# dabpi__v11.net
KiCad netlist of a schematic drawn in EAGLE
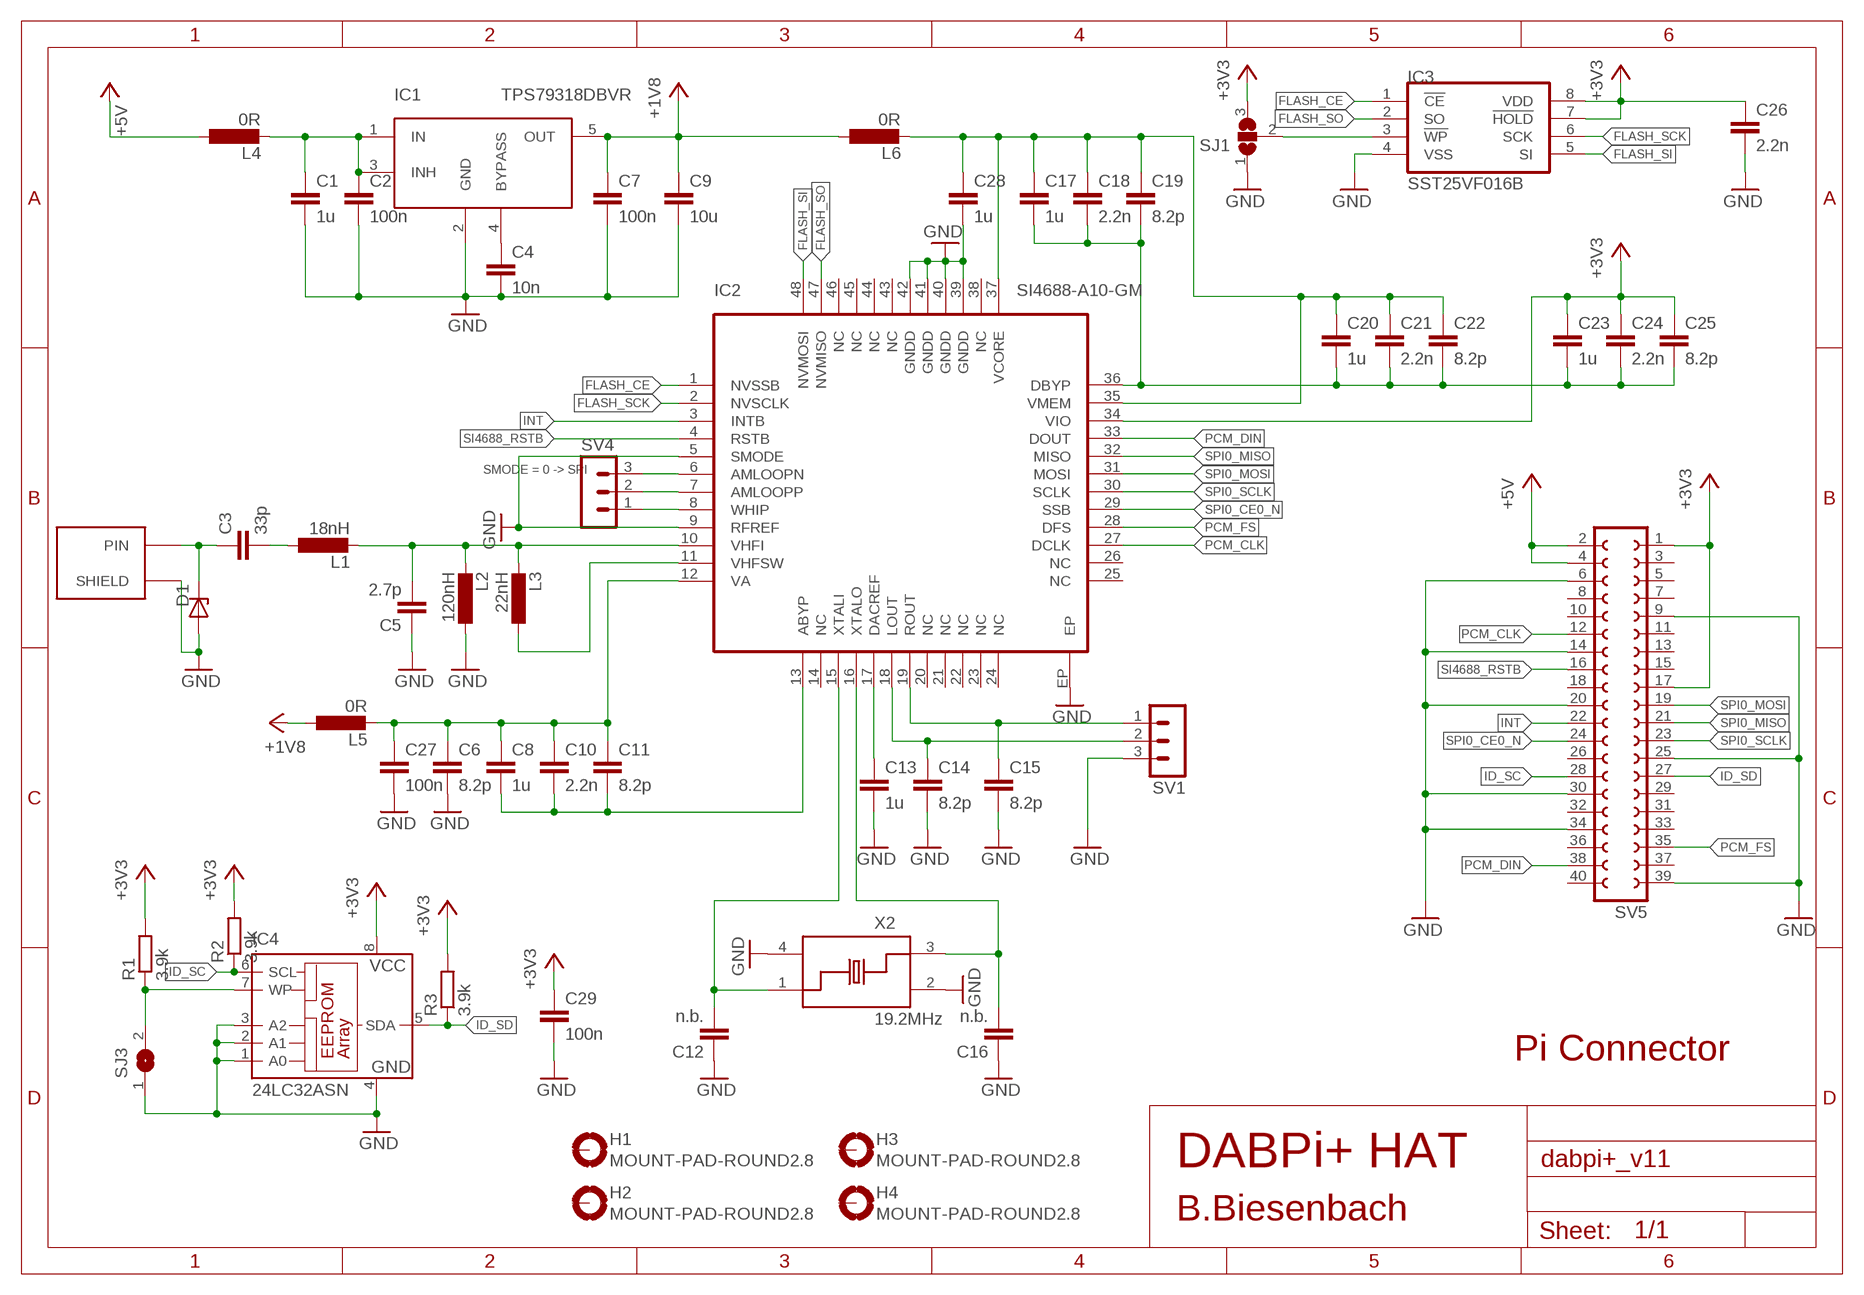
[diagram p0: schematic, sheet 1]

(export (version "E")
  (design (tool "Eeschema 10.0.6"))
  (components
    (comp (ref "C1")
      (value "1u")
      (footprint "eagle-import:SMD0603")
      (libsource (lib "eagle-import") (part "C0603"))
    )
    (comp (ref "C2")
      (value "100n")
      (footprint "eagle-import:SMD0603")
      (libsource (lib "eagle-import") (part "C0603"))
    )
    (comp (ref "C3")
      (value "33p")
      (footprint "eagle-import:SMD0402")
      (libsource (lib "eagle-import") (part "C0402"))
    )
    (comp (ref "C4")
      (value "10n")
      (footprint "eagle-import:SMD0603")
      (libsource (lib "eagle-import") (part "C0603"))
    )
    (comp (ref "C5")
      (value "2.7p")
      (footprint "eagle-import:SMD0402")
      (libsource (lib "eagle-import") (part "C0402"))
    )
    (comp (ref "C6")
      (value "8.2p")
      (footprint "eagle-import:SMD0603")
      (libsource (lib "eagle-import") (part "C0603"))
    )
    (comp (ref "C7")
      (value "100n")
      (footprint "eagle-import:SMD0603")
      (libsource (lib "eagle-import") (part "C0603"))
    )
    (comp (ref "C8")
      (value "1u")
      (footprint "eagle-import:SMD0603")
      (libsource (lib "eagle-import") (part "C0603"))
    )
    (comp (ref "C9")
      (value "10u")
      (footprint "eagle-import:SMD0603")
      (libsource (lib "eagle-import") (part "C0603"))
    )
    (comp (ref "C10")
      (value "2.2n")
      (footprint "eagle-import:SMD0603")
      (libsource (lib "eagle-import") (part "C0603"))
    )
    (comp (ref "C11")
      (value "8.2p")
      (footprint "eagle-import:SMD0603")
      (libsource (lib "eagle-import") (part "C0603"))
    )
    (comp (ref "C12")
      (value "n.b.")
      (footprint "eagle-import:SMD0402")
      (libsource (lib "eagle-import") (part "C0402"))
    )
    (comp (ref "C13")
      (value "1u")
      (footprint "eagle-import:SMD0603")
      (libsource (lib "eagle-import") (part "C0603"))
    )
    (comp (ref "C14")
      (value "8.2p")
      (footprint "eagle-import:SMD0603")
      (libsource (lib "eagle-import") (part "C0603"))
    )
    (comp (ref "C15")
      (value "8.2p")
      (footprint "eagle-import:SMD0603")
      (libsource (lib "eagle-import") (part "C0603"))
    )
    (comp (ref "C16")
      (value "n.b.")
      (footprint "eagle-import:SMD0402")
      (libsource (lib "eagle-import") (part "C0402"))
    )
    (comp (ref "C17")
      (value "1u")
      (footprint "eagle-import:SMD0603")
      (libsource (lib "eagle-import") (part "C0603"))
    )
    (comp (ref "C18")
      (value "2.2n")
      (footprint "eagle-import:SMD0603")
      (libsource (lib "eagle-import") (part "C0603"))
    )
    (comp (ref "C19")
      (value "8.2p")
      (footprint "eagle-import:SMD0603")
      (libsource (lib "eagle-import") (part "C0603"))
    )
    (comp (ref "C20")
      (value "1u")
      (footprint "eagle-import:SMD0603")
      (libsource (lib "eagle-import") (part "C0603"))
    )
    (comp (ref "C21")
      (value "2.2n")
      (footprint "eagle-import:SMD0603")
      (libsource (lib "eagle-import") (part "C0603"))
    )
    (comp (ref "C22")
      (value "8.2p")
      (footprint "eagle-import:SMD0603")
      (libsource (lib "eagle-import") (part "C0603"))
    )
    (comp (ref "C23")
      (value "1u")
      (footprint "eagle-import:SMD0603")
      (libsource (lib "eagle-import") (part "C0603"))
    )
    (comp (ref "C24")
      (value "2.2n")
      (footprint "eagle-import:SMD0603")
      (libsource (lib "eagle-import") (part "C0603"))
    )
    (comp (ref "C25")
      (value "8.2p")
      (footprint "eagle-import:SMD0603")
      (libsource (lib "eagle-import") (part "C0603"))
    )
    (comp (ref "C26")
      (value "2.2n")
      (footprint "eagle-import:SMD0603")
      (libsource (lib "eagle-import") (part "C0603"))
    )
    (comp (ref "C27")
      (value "100n")
      (footprint "eagle-import:SMD0603")
      (libsource (lib "eagle-import") (part "C0603"))
    )
    (comp (ref "C28")
      (value "1u")
      (footprint "eagle-import:SMD0603")
      (libsource (lib "eagle-import") (part "C0603"))
    )
    (comp (ref "C29")
      (value "100n")
      (footprint "eagle-import:SMD0603")
      (libsource (lib "eagle-import") (part "C0603"))
    )
    (comp (ref "D1")
      (value "ESD9L5.0")
      (footprint "eagle-import:SOD923")
      (libsource (lib "eagle-import") (part "ESD9L5.0"))
    )
    (comp (ref "H1")
      (value "MOUNT-PAD-ROUND2.8")
      (footprint "eagle-import:2,8-PAD")
      (libsource (lib "eagle-import") (part "MOUNT-PAD-ROUND2.8"))
    )
    (comp (ref "H2")
      (value "MOUNT-PAD-ROUND2.8")
      (footprint "eagle-import:2,8-PAD")
      (libsource (lib "eagle-import") (part "MOUNT-PAD-ROUND2.8"))
    )
    (comp (ref "H3")
      (value "MOUNT-PAD-ROUND2.8")
      (footprint "eagle-import:2,8-PAD")
      (libsource (lib "eagle-import") (part "MOUNT-PAD-ROUND2.8"))
    )
    (comp (ref "H4")
      (value "MOUNT-PAD-ROUND2.8")
      (footprint "eagle-import:2,8-PAD")
      (libsource (lib "eagle-import") (part "MOUNT-PAD-ROUND2.8"))
    )
    (comp (ref "IC1")
      (value "TPS79318DBVR")
      (footprint "eagle-import:SOT23-5")
      (libsource (lib "eagle-import") (part "TPS79318DBVR"))
    )
    (comp (ref "IC2")
      (value "SI4688-A10-GM")
      (footprint "eagle-import:QFN48")
      (libsource (lib "eagle-import") (part "SI4688-A10-GM"))
    )
    (comp (ref "IC3")
      (value "SST25VF016B")
      (footprint "eagle-import:SO08")
      (libsource (lib "eagle-import") (part "SST25VF016B"))
    )
    (comp (ref "IC4")
      (value "24LC32ASN")
      (footprint "eagle-import:SO-08")
      (fields (field (name "MF") "MICROCHIP") (field (name "MPN") "24LC32A/SN"))
      (libsource (lib "eagle-import") (part "24SNLC32A"))
    )
    (comp (ref "L1")
      (value "18nH")
      (footprint "eagle-import:SMD0402")
      (libsource (lib "eagle-import") (part "L0402"))
    )
    (comp (ref "L2")
      (value "120nH")
      (footprint "eagle-import:SMD0402")
      (libsource (lib "eagle-import") (part "L0402"))
    )
    (comp (ref "L3")
      (value "22nH")
      (footprint "eagle-import:SMD0402")
      (libsource (lib "eagle-import") (part "L0402"))
    )
    (comp (ref "L4")
      (value "0R")
      (footprint "eagle-import:SMD0603")
      (libsource (lib "eagle-import") (part "L0603"))
    )
    (comp (ref "L5")
      (value "0R")
      (footprint "eagle-import:SMD0603")
      (libsource (lib "eagle-import") (part "L0603"))
    )
    (comp (ref "L6")
      (value "0R")
      (footprint "eagle-import:SMD0603")
      (libsource (lib "eagle-import") (part "L0603"))
    )
    (comp (ref "R1")
      (value "3.9k")
      (footprint "eagle-import:SMD0603")
      (libsource (lib "eagle-import") (part "R0603"))
    )
    (comp (ref "R2")
      (value "3.9k")
      (footprint "eagle-import:SMD0603")
      (libsource (lib "eagle-import") (part "R0603"))
    )
    (comp (ref "R3")
      (value "3.9k")
      (footprint "eagle-import:SMD0603")
      (libsource (lib "eagle-import") (part "R0603"))
    )
    (comp (ref "SJ1")
      (value "SJ2W")
      (footprint "eagle-import:SJ_2")
      (libsource (lib "eagle-import") (part "SJ2W"))
    )
    (comp (ref "SJ3") (value "SJ") (footprint "eagle-import:SJ") (libsource (lib "eagle-import") (part "SJ")))
    (comp (ref "SV1")
      (value "MA03-1")
      (footprint "eagle-import:MA03-1")
      (libsource (lib "eagle-import") (part "MA03-1"))
    )
    (comp (ref "SV4")
      (value "MA03-1")
      (footprint "eagle-import:MA03-1")
      (libsource (lib "eagle-import") (part "MA03-1"))
    )
    (comp (ref "SV5")
      (value "FE20-2")
      (footprint "eagle-import:FE20-2")
      (libsource (lib "eagle-import") (part "FE20-2"))
    )
    (comp (ref "X1")
      (value "SMA_LP_1.57MM")
      (footprint "eagle-import:SMA_LP_1.57MM")
      (libsource (lib "eagle-import") (part "SMA_LP_1.57MM"))
    )
    (comp (ref "X2")
      (value "19.2MHz")
      (footprint "eagle-import:XTAL_3.2X2.5")
      (libsource (lib "eagle-import") (part "XTAL_3.2X2.5"))
    )
  )
  (nets
    (net (code "1") (name "+1V8") (class "Default")
      (node (ref "C7") (pin "1") (pinfunction "1_1") (pintype "passive"))
      (node (ref "C9") (pin "1") (pinfunction "1_1") (pintype "passive"))
      (node (ref "IC1") (pin "5") (pinfunction "OUT_5") (pintype "power_in"))
      (node (ref "L5") (pin "1") (pinfunction "1_1") (pintype "passive"))
      (node (ref "L6") (pin "1") (pinfunction "1_1") (pintype "passive"))
    )
    (net (code "2") (name "+3V3") (class "Default")
      (node (ref "C23") (pin "1") (pinfunction "1_1") (pintype "passive"))
      (node (ref "C24") (pin "1") (pinfunction "1_1") (pintype "passive"))
      (node (ref "C25") (pin "1") (pinfunction "1_1") (pintype "passive"))
      (node (ref "C26") (pin "1") (pinfunction "1_1") (pintype "passive"))
      (node (ref "C29") (pin "1") (pinfunction "1_1") (pintype "passive"))
      (node (ref "IC2") (pin "34") (pinfunction "VIO_34") (pintype "power_in"))
      (node (ref "IC3") (pin "7") (pinfunction "~{HOLD}_7") (pintype "input"))
      (node (ref "IC3") (pin "8") (pinfunction "VDD_8") (pintype "power_in"))
      (node (ref "IC4") (pin "8") (pinfunction "VCC_8") (pintype "power_in"))
      (node (ref "R1") (pin "2") (pinfunction "2_2") (pintype "passive"))
      (node (ref "R2") (pin "2") (pinfunction "2_2") (pintype "passive"))
      (node (ref "R3") (pin "2") (pinfunction "2_2") (pintype "passive"))
      (node (ref "SJ1") (pin "3") (pinfunction "3_3") (pintype "passive"))
      (node (ref "SV5") (pin "1") (pinfunction "1_1") (pintype "passive"))
      (node (ref "SV5") (pin "17") (pinfunction "17_17") (pintype "passive"))
    )
    (net (code "3") (name "+5V") (class "Default")
      (node (ref "L4") (pin "1") (pinfunction "1_1") (pintype "passive"))
      (node (ref "SV5") (pin "2") (pinfunction "2_2") (pintype "passive"))
      (node (ref "SV5") (pin "4") (pinfunction "4_4") (pintype "passive"))
    )
    (net (code "4") (name "FLASH_CE") (class "Default")
      (node (ref "IC2") (pin "1") (pinfunction "NVSSB_1") (pintype "output"))
      (node (ref "IC3") (pin "1") (pinfunction "~{CE}_1") (pintype "input"))
    )
    (net (code "5") (name "FLASH_SCK") (class "Default")
      (node (ref "IC2") (pin "2") (pinfunction "NVSCLK_2") (pintype "output"))
      (node (ref "IC3") (pin "6") (pinfunction "SCK_6") (pintype "input"))
    )
    (net (code "6") (name "FLASH_SI") (class "Default")
      (node (ref "IC2") (pin "48") (pinfunction "NVMOSI_48") (pintype "output"))
      (node (ref "IC3") (pin "5") (pinfunction "SI_5") (pintype "input"))
    )
    (net (code "7") (name "FLASH_SO") (class "Default")
      (node (ref "IC2") (pin "47") (pinfunction "NVMISO_47") (pintype "input"))
      (node (ref "IC3") (pin "2") (pinfunction "SO_2") (pintype "output"))
    )
    (net (code "8") (name "GND") (class "Default")
      (node (ref "C1") (pin "2") (pinfunction "2_2") (pintype "passive"))
      (node (ref "C12") (pin "1") (pinfunction "1_1") (pintype "passive"))
      (node (ref "C13") (pin "2") (pinfunction "2_2") (pintype "passive"))
      (node (ref "C14") (pin "2") (pinfunction "2_2") (pintype "passive"))
      (node (ref "C15") (pin "2") (pinfunction "2_2") (pintype "passive"))
      (node (ref "C16") (pin "1") (pinfunction "1_1") (pintype "passive"))
      (node (ref "C2") (pin "2") (pinfunction "2_2") (pintype "passive"))
      (node (ref "C26") (pin "2") (pinfunction "2_2") (pintype "passive"))
      (node (ref "C27") (pin "2") (pinfunction "2_2") (pintype "passive"))
      (node (ref "C28") (pin "2") (pinfunction "2_2") (pintype "passive"))
      (node (ref "C29") (pin "2") (pinfunction "2_2") (pintype "passive"))
      (node (ref "C4") (pin "2") (pinfunction "2_2") (pintype "passive"))
      (node (ref "C5") (pin "1") (pinfunction "1_1") (pintype "passive"))
      (node (ref "C6") (pin "2") (pinfunction "2_2") (pintype "passive"))
      (node (ref "C7") (pin "2") (pinfunction "2_2") (pintype "passive"))
      (node (ref "C9") (pin "2") (pinfunction "2_2") (pintype "passive"))
      (node (ref "D1") (pin "A") (pinfunction "A_A") (pintype "passive"))
      (node (ref "IC1") (pin "2") (pinfunction "GND_2") (pintype "power_in"))
      (node (ref "IC2") (pin "39") (pinfunction "GNDD_39") (pintype "power_in"))
      (node (ref "IC2") (pin "40") (pinfunction "GNDD_40") (pintype "power_in"))
      (node (ref "IC2") (pin "41") (pinfunction "GNDD_41") (pintype "power_in"))
      (node (ref "IC2") (pin "42") (pinfunction "GNDD_42") (pintype "power_in"))
      (node (ref "IC2") (pin "5") (pinfunction "SMODE_5") (pintype "input"))
      (node (ref "IC2") (pin "9") (pinfunction "RFREF_9") (pintype "power_in"))
      (node (ref "IC2") (pin "EP") (pinfunction "EP_EP") (pintype "bidirectional"))
      (node (ref "IC3") (pin "4") (pinfunction "VSS_4") (pintype "power_in"))
      (node (ref "IC4") (pin "1") (pinfunction "A0_1") (pintype "input"))
      (node (ref "IC4") (pin "2") (pinfunction "A1_2") (pintype "input"))
      (node (ref "IC4") (pin "3") (pinfunction "A2_3") (pintype "input"))
      (node (ref "IC4") (pin "4") (pinfunction "GND_4") (pintype "power_in"))
      (node (ref "L2") (pin "1") (pinfunction "1_1") (pintype "passive"))
      (node (ref "SJ1") (pin "1") (pinfunction "1_1") (pintype "passive"))
      (node (ref "SJ3") (pin "1") (pinfunction "1_1") (pintype "passive"))
      (node (ref "SV1") (pin "3") (pinfunction "3_3") (pintype "passive"))
      (node (ref "SV5") (pin "14") (pinfunction "14_14") (pintype "passive"))
      (node (ref "SV5") (pin "20") (pinfunction "20_20") (pintype "passive"))
      (node (ref "SV5") (pin "25") (pinfunction "25_25") (pintype "passive"))
      (node (ref "SV5") (pin "30") (pinfunction "30_30") (pintype "passive"))
      (node (ref "SV5") (pin "34") (pinfunction "34_34") (pintype "passive"))
      (node (ref "SV5") (pin "39") (pinfunction "39_39") (pintype "passive"))
      (node (ref "SV5") (pin "6") (pinfunction "6_6") (pintype "passive"))
      (node (ref "SV5") (pin "9") (pinfunction "9_9") (pintype "passive"))
      (node (ref "X1") (pin "GND") (pinfunction "SHIELD_GND") (pintype "power_in"))
      (node (ref "X1") (pin "GND@1") (pinfunction "SHIELD_GND@1") (pintype "power_in"))
      (node (ref "X1") (pin "GND@2") (pinfunction "SHIELD_GND@2") (pintype "power_in"))
      (node (ref "X1") (pin "GND@3") (pinfunction "SHIELD_GND@3") (pintype "power_in"))
      (node (ref "X2") (pin "2") (pinfunction "GND_2") (pintype "power_in"))
      (node (ref "X2") (pin "4") (pinfunction "GND_4") (pintype "power_in"))
    )
    (net (code "9") (name "ID_SC") (class "Default")
      (node (ref "IC4") (pin "6") (pinfunction "SCL_6") (pintype "input"))
      (node (ref "R2") (pin "1") (pinfunction "1_1") (pintype "passive"))
      (node (ref "SV5") (pin "28") (pinfunction "28_28") (pintype "passive"))
    )
    (net (code "10") (name "ID_SD") (class "Default")
      (node (ref "IC4") (pin "5") (pinfunction "SDA_5") (pintype "bidirectional"))
      (node (ref "R3") (pin "1") (pinfunction "1_1") (pintype "passive"))
      (node (ref "SV5") (pin "27") (pinfunction "27_27") (pintype "passive"))
    )
    (net (code "11") (name "INT") (class "Default")
      (node (ref "IC2") (pin "3") (pinfunction "INTB_3") (pintype "output"))
      (node (ref "SV5") (pin "22") (pinfunction "22_22") (pintype "passive"))
    )
    (net (code "12") (name "Net-(C3-Pad2)") (class "Default")
      (node (ref "C3") (pin "2") (pinfunction "2_2") (pintype "passive"))
      (node (ref "L1") (pin "1") (pinfunction "1_1") (pintype "passive"))
    )
    (net (code "13") (name "Net-(D1-C)") (class "Default")
      (node (ref "C3") (pin "1") (pinfunction "1_1") (pintype "passive"))
      (node (ref "D1") (pin "K") (pinfunction "C_K") (pintype "passive"))
      (node (ref "X1") (pin "PIN") (pinfunction "PIN_PIN") (pintype "passive"))
    )
    (net (code "14") (name "Net-(IC1-BYPASS)") (class "Default")
      (node (ref "C4") (pin "1") (pinfunction "1_1") (pintype "passive"))
      (node (ref "IC1") (pin "4") (pinfunction "BYPASS_4") (pintype "power_in"))
    )
    (net (code "15") (name "Net-(IC1-IN)") (class "Default")
      (node (ref "C1") (pin "1") (pinfunction "1_1") (pintype "passive"))
      (node (ref "C2") (pin "1") (pinfunction "1_1") (pintype "passive"))
      (node (ref "IC1") (pin "1") (pinfunction "IN_1") (pintype "power_in"))
      (node (ref "IC1") (pin "3") (pinfunction "INH_3") (pintype "input"))
      (node (ref "L4") (pin "2") (pinfunction "2_2") (pintype "passive"))
    )
    (net (code "16") (name "Net-(IC2-ABYP)") (class "Default")
      (node (ref "C10") (pin "2") (pinfunction "2_2") (pintype "passive"))
      (node (ref "C11") (pin "2") (pinfunction "2_2") (pintype "passive"))
      (node (ref "C8") (pin "2") (pinfunction "2_2") (pintype "passive"))
      (node (ref "IC2") (pin "13") (pinfunction "ABYP_13") (pintype "power_in"))
    )
    (net (code "17") (name "Net-(IC2-AMLOOPN)") (class "Default")
      (node (ref "IC2") (pin "6") (pinfunction "AMLOOPN_6") (pintype "power_in"))
      (node (ref "SV4") (pin "3") (pinfunction "3_3") (pintype "passive"))
    )
    (net (code "18") (name "Net-(IC2-AMLOOPP)") (class "Default")
      (node (ref "IC2") (pin "7") (pinfunction "AMLOOPP_7") (pintype "power_in"))
      (node (ref "SV4") (pin "2") (pinfunction "2_2") (pintype "passive"))
    )
    (net (code "19") (name "Net-(IC2-DACREF)") (class "Default")
      (node (ref "C13") (pin "1") (pinfunction "1_1") (pintype "passive"))
      (node (ref "IC2") (pin "17") (pinfunction "DACREF_17") (pintype "power_in"))
    )
    (net (code "20") (name "Net-(IC2-DBYP)") (class "Default")
      (node (ref "C17") (pin "2") (pinfunction "2_2") (pintype "passive"))
      (node (ref "C18") (pin "2") (pinfunction "2_2") (pintype "passive"))
      (node (ref "C19") (pin "2") (pinfunction "2_2") (pintype "passive"))
      (node (ref "C20") (pin "2") (pinfunction "2_2") (pintype "passive"))
      (node (ref "C21") (pin "2") (pinfunction "2_2") (pintype "passive"))
      (node (ref "C22") (pin "2") (pinfunction "2_2") (pintype "passive"))
      (node (ref "C23") (pin "2") (pinfunction "2_2") (pintype "passive"))
      (node (ref "C24") (pin "2") (pinfunction "2_2") (pintype "passive"))
      (node (ref "C25") (pin "2") (pinfunction "2_2") (pintype "passive"))
      (node (ref "IC2") (pin "36") (pinfunction "DBYP_36") (pintype "power_in"))
    )
    (net (code "21") (name "Net-(IC2-LOUT)") (class "Default")
      (node (ref "C14") (pin "1") (pinfunction "1_1") (pintype "passive"))
      (node (ref "IC2") (pin "18") (pinfunction "LOUT_18") (pintype "output"))
      (node (ref "SV1") (pin "2") (pinfunction "2_2") (pintype "passive"))
    )
    (net (code "22") (name "Net-(IC2-ROUT)") (class "Default")
      (node (ref "C15") (pin "1") (pinfunction "1_1") (pintype "passive"))
      (node (ref "IC2") (pin "19") (pinfunction "ROUT_19") (pintype "output"))
      (node (ref "SV1") (pin "1") (pinfunction "1_1") (pintype "passive"))
    )
    (net (code "23") (name "Net-(IC2-VA)") (class "Default")
      (node (ref "C10") (pin "1") (pinfunction "1_1") (pintype "passive"))
      (node (ref "C11") (pin "1") (pinfunction "1_1") (pintype "passive"))
      (node (ref "C27") (pin "1") (pinfunction "1_1") (pintype "passive"))
      (node (ref "C6") (pin "1") (pinfunction "1_1") (pintype "passive"))
      (node (ref "C8") (pin "1") (pinfunction "1_1") (pintype "passive"))
      (node (ref "IC2") (pin "12") (pinfunction "VA_12") (pintype "power_in"))
      (node (ref "L5") (pin "2") (pinfunction "2_2") (pintype "passive"))
    )
    (net (code "24") (name "Net-(IC2-VCORE)") (class "Default")
      (node (ref "C17") (pin "1") (pinfunction "1_1") (pintype "passive"))
      (node (ref "C18") (pin "1") (pinfunction "1_1") (pintype "passive"))
      (node (ref "C19") (pin "1") (pinfunction "1_1") (pintype "passive"))
      (node (ref "C20") (pin "1") (pinfunction "1_1") (pintype "passive"))
      (node (ref "C21") (pin "1") (pinfunction "1_1") (pintype "passive"))
      (node (ref "C22") (pin "1") (pinfunction "1_1") (pintype "passive"))
      (node (ref "C28") (pin "1") (pinfunction "1_1") (pintype "passive"))
      (node (ref "IC2") (pin "35") (pinfunction "VMEM_35") (pintype "power_in"))
      (node (ref "IC2") (pin "37") (pinfunction "VCORE_37") (pintype "power_in"))
      (node (ref "L6") (pin "2") (pinfunction "2_2") (pintype "passive"))
    )
    (net (code "25") (name "Net-(IC2-VHFI)") (class "Default")
      (node (ref "C5") (pin "2") (pinfunction "2_2") (pintype "passive"))
      (node (ref "IC2") (pin "10") (pinfunction "VHFI_10") (pintype "input"))
      (node (ref "L1") (pin "2") (pinfunction "2_2") (pintype "passive"))
      (node (ref "L2") (pin "2") (pinfunction "2_2") (pintype "passive"))
      (node (ref "L3") (pin "2") (pinfunction "2_2") (pintype "passive"))
    )
    (net (code "26") (name "Net-(IC2-VHFSW)") (class "Default")
      (node (ref "IC2") (pin "11") (pinfunction "VHFSW_11") (pintype "output"))
      (node (ref "L3") (pin "1") (pinfunction "1_1") (pintype "passive"))
    )
    (net (code "27") (name "Net-(IC2-WHIP)") (class "Default")
      (node (ref "IC2") (pin "8") (pinfunction "WHIP_8") (pintype "power_in"))
      (node (ref "SV4") (pin "1") (pinfunction "1_1") (pintype "passive"))
    )
    (net (code "28") (name "Net-(IC2-XTALI)") (class "Default")
      (node (ref "C12") (pin "2") (pinfunction "2_2") (pintype "passive"))
      (node (ref "IC2") (pin "15") (pinfunction "XTALI_15") (pintype "input"))
      (node (ref "X2") (pin "1") (pinfunction "1_1") (pintype "passive"))
    )
    (net (code "29") (name "Net-(IC2-XTALO)") (class "Default")
      (node (ref "C16") (pin "2") (pinfunction "2_2") (pintype "passive"))
      (node (ref "IC2") (pin "16") (pinfunction "XTALO_16") (pintype "output"))
      (node (ref "X2") (pin "3") (pinfunction "3_3") (pintype "passive"))
    )
    (net (code "30") (name "Net-(IC3-~{WP})") (class "Default")
      (node (ref "IC3") (pin "3") (pinfunction "~{WP}_3") (pintype "input"))
      (node (ref "SJ1") (pin "2") (pinfunction "2_2") (pintype "passive"))
    )
    (net (code "31") (name "Net-(IC4-WP)") (class "Default")
      (node (ref "IC4") (pin "7") (pinfunction "WP_7") (pintype "input"))
      (node (ref "R1") (pin "1") (pinfunction "1_1") (pintype "passive"))
      (node (ref "SJ3") (pin "2") (pinfunction "2_2") (pintype "passive"))
    )
    (net (code "32") (name "PCM_CLK") (class "Default")
      (node (ref "IC2") (pin "27") (pinfunction "DCLK_27") (pintype "bidirectional"))
      (node (ref "SV5") (pin "12") (pinfunction "12_12") (pintype "passive"))
    )
    (net (code "33") (name "PCM_DIN") (class "Default")
      (node (ref "IC2") (pin "33") (pinfunction "DOUT_33") (pintype "output"))
      (node (ref "SV5") (pin "38") (pinfunction "38_38") (pintype "passive"))
    )
    (net (code "34") (name "PCM_FS") (class "Default")
      (node (ref "IC2") (pin "28") (pinfunction "DFS_28") (pintype "bidirectional"))
      (node (ref "SV5") (pin "35") (pinfunction "35_35") (pintype "passive"))
    )
    (net (code "35") (name "SI4688_RSTB") (class "Default")
      (node (ref "IC2") (pin "4") (pinfunction "RSTB_4") (pintype "input"))
      (node (ref "SV5") (pin "16") (pinfunction "16_16") (pintype "passive"))
    )
    (net (code "36") (name "SPI0_CE0_N") (class "Default")
      (node (ref "IC2") (pin "29") (pinfunction "SSB_29") (pintype "input"))
      (node (ref "SV5") (pin "24") (pinfunction "24_24") (pintype "passive"))
    )
    (net (code "37") (name "SPI0_MISO") (class "Default")
      (node (ref "IC2") (pin "32") (pinfunction "MISO_32") (pintype "bidirectional"))
      (node (ref "SV5") (pin "21") (pinfunction "21_21") (pintype "passive"))
    )
    (net (code "38") (name "SPI0_MOSI") (class "Default")
      (node (ref "IC2") (pin "31") (pinfunction "MOSI_31") (pintype "bidirectional"))
      (node (ref "SV5") (pin "19") (pinfunction "19_19") (pintype "passive"))
    )
    (net (code "39") (name "SPI0_SCLK") (class "Default")
      (node (ref "IC2") (pin "30") (pinfunction "SCLK_30") (pintype "input"))
      (node (ref "SV5") (pin "23") (pinfunction "23_23") (pintype "passive"))
    )
    (net (code "40") (name "unconnected-(H1-MOUNT-PadB2,8)") (class "Default")
      (node (ref "H1") (pin "B2,8") (pinfunction "MOUNT_B2,8") (pintype "passive"))
    )
    (net (code "41") (name "unconnected-(H2-MOUNT-PadB2,8)") (class "Default")
      (node (ref "H2") (pin "B2,8") (pinfunction "MOUNT_B2,8") (pintype "passive"))
    )
    (net (code "42") (name "unconnected-(H3-MOUNT-PadB2,8)") (class "Default")
      (node (ref "H3") (pin "B2,8") (pinfunction "MOUNT_B2,8") (pintype "passive"))
    )
    (net (code "43") (name "unconnected-(H4-MOUNT-PadB2,8)") (class "Default")
      (node (ref "H4") (pin "B2,8") (pinfunction "MOUNT_B2,8") (pintype "passive"))
    )
    (net (code "44") (name "unconnected-(IC2-NC-Pad14)") (class "Default")
      (node (ref "IC2") (pin "14") (pinfunction "NC_14") (pintype "no_connect"))
    )
    (net (code "45") (name "unconnected-(IC2-NC-Pad20)") (class "Default")
      (node (ref "IC2") (pin "20") (pinfunction "NC_20") (pintype "no_connect"))
    )
    (net (code "46") (name "unconnected-(IC2-NC-Pad21)") (class "Default")
      (node (ref "IC2") (pin "21") (pinfunction "NC_21") (pintype "no_connect"))
    )
    (net (code "47") (name "unconnected-(IC2-NC-Pad22)") (class "Default")
      (node (ref "IC2") (pin "22") (pinfunction "NC_22") (pintype "no_connect"))
    )
    (net (code "48") (name "unconnected-(IC2-NC-Pad23)") (class "Default")
      (node (ref "IC2") (pin "23") (pinfunction "NC_23") (pintype "no_connect"))
    )
    (net (code "49") (name "unconnected-(IC2-NC-Pad24)") (class "Default")
      (node (ref "IC2") (pin "24") (pinfunction "NC_24") (pintype "no_connect"))
    )
    (net (code "50") (name "unconnected-(IC2-NC-Pad25)") (class "Default")
      (node (ref "IC2") (pin "25") (pinfunction "NC_25") (pintype "no_connect"))
    )
    (net (code "51") (name "unconnected-(IC2-NC-Pad26)") (class "Default")
      (node (ref "IC2") (pin "26") (pinfunction "NC_26") (pintype "no_connect"))
    )
    (net (code "52") (name "unconnected-(IC2-NC-Pad38)") (class "Default")
      (node (ref "IC2") (pin "38") (pinfunction "NC_38") (pintype "no_connect"))
    )
    (net (code "53") (name "unconnected-(IC2-NC-Pad43)") (class "Default")
      (node (ref "IC2") (pin "43") (pinfunction "NC_43") (pintype "no_connect"))
    )
    (net (code "54") (name "unconnected-(IC2-NC-Pad44)") (class "Default")
      (node (ref "IC2") (pin "44") (pinfunction "NC_44") (pintype "no_connect"))
    )
    (net (code "55") (name "unconnected-(IC2-NC-Pad45)") (class "Default")
      (node (ref "IC2") (pin "45") (pinfunction "NC_45") (pintype "no_connect"))
    )
    (net (code "56") (name "unconnected-(IC2-NC-Pad46)") (class "Default")
      (node (ref "IC2") (pin "46") (pinfunction "NC_46") (pintype "no_connect"))
    )
    (net (code "57") (name "unconnected-(SV5-Pad3)") (class "Default")
      (node (ref "SV5") (pin "3") (pinfunction "3_3") (pintype "passive"))
    )
    (net (code "58") (name "unconnected-(SV5-Pad5)") (class "Default")
      (node (ref "SV5") (pin "5") (pinfunction "5_5") (pintype "passive"))
    )
    (net (code "59") (name "unconnected-(SV5-Pad7)") (class "Default")
      (node (ref "SV5") (pin "7") (pinfunction "7_7") (pintype "passive"))
    )
    (net (code "60") (name "unconnected-(SV5-Pad8)") (class "Default")
      (node (ref "SV5") (pin "8") (pinfunction "8_8") (pintype "passive"))
    )
    (net (code "61") (name "unconnected-(SV5-Pad10)") (class "Default")
      (node (ref "SV5") (pin "10") (pinfunction "10_10") (pintype "passive"))
    )
    (net (code "62") (name "unconnected-(SV5-Pad11)") (class "Default")
      (node (ref "SV5") (pin "11") (pinfunction "11_11") (pintype "passive"))
    )
    (net (code "63") (name "unconnected-(SV5-Pad13)") (class "Default")
      (node (ref "SV5") (pin "13") (pinfunction "13_13") (pintype "passive"))
    )
    (net (code "64") (name "unconnected-(SV5-Pad15)") (class "Default")
      (node (ref "SV5") (pin "15") (pinfunction "15_15") (pintype "passive"))
    )
    (net (code "65") (name "unconnected-(SV5-Pad18)") (class "Default")
      (node (ref "SV5") (pin "18") (pinfunction "18_18") (pintype "passive"))
    )
    (net (code "66") (name "unconnected-(SV5-Pad26)") (class "Default")
      (node (ref "SV5") (pin "26") (pinfunction "26_26") (pintype "passive"))
    )
    (net (code "67") (name "unconnected-(SV5-Pad29)") (class "Default")
      (node (ref "SV5") (pin "29") (pinfunction "29_29") (pintype "passive"))
    )
    (net (code "68") (name "unconnected-(SV5-Pad31)") (class "Default")
      (node (ref "SV5") (pin "31") (pinfunction "31_31") (pintype "passive"))
    )
    (net (code "69") (name "unconnected-(SV5-Pad32)") (class "Default")
      (node (ref "SV5") (pin "32") (pinfunction "32_32") (pintype "passive"))
    )
    (net (code "70") (name "unconnected-(SV5-Pad33)") (class "Default")
      (node (ref "SV5") (pin "33") (pinfunction "33_33") (pintype "passive"))
    )
    (net (code "71") (name "unconnected-(SV5-Pad36)") (class "Default")
      (node (ref "SV5") (pin "36") (pinfunction "36_36") (pintype "passive"))
    )
    (net (code "72") (name "unconnected-(SV5-Pad37)") (class "Default")
      (node (ref "SV5") (pin "37") (pinfunction "37_37") (pintype "passive"))
    )
    (net (code "73") (name "unconnected-(SV5-Pad40)") (class "Default")
      (node (ref "SV5") (pin "40") (pinfunction "40_40") (pintype "passive"))
    )
  )
)
